# MouseGoggles_IRLED-1-5.net
KiCad netlist of a schematic drawn in EAGLE
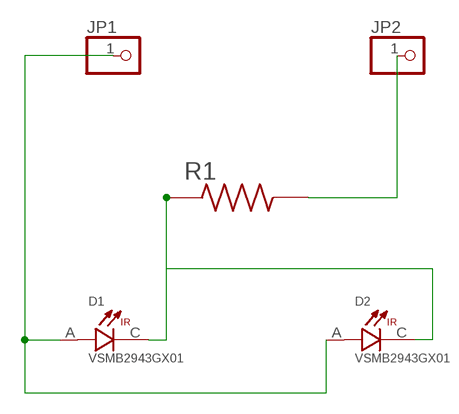
[diagram p0: schematic, sheet 1]

(export (version "E")
  (design (tool "Eeschema 10.0.6"))
  (components
    (comp (ref "D1")
      (value "VSMB2943GX01")
      (footprint "eagle-import:DIO_VSMB2943GX01")
      (fields (field (name "MANUFACTURER") "VISHAY"))
      (libsource (lib "eagle-import") (part "VSMB2943GX01"))
    )
    (comp (ref "D2")
      (value "VSMB2943GX01")
      (footprint "eagle-import:DIO_VSMB2943GX01")
      (fields (field (name "MANUFACTURER") "VISHAY"))
      (libsource (lib "eagle-import") (part "VSMB2943GX01"))
    )
    (comp (ref "JP1")
      (value "PINHD-1X1")
      (footprint "eagle-import:1X01")
      (libsource (lib "eagle-import") (part "PINHD-1X1"))
    )
    (comp (ref "JP2")
      (value "PINHD-1X1")
      (footprint "eagle-import:1X01")
      (libsource (lib "eagle-import") (part "PINHD-1X1"))
    )
    (comp (ref "R1")
      (value "RC0805FR-07100RL")
      (footprint "eagle-import:RESC2012X60N")
      (libsource (lib "eagle-import") (part "RC0805FR-07100RL"))
    )
  )
  (nets
    (net (code "1") (name "Net-(D1-PadA)") (class "Default")
      (node (ref "D1") (pin "A") (pinfunction "A_A") (pintype "passive"))
      (node (ref "D2") (pin "A") (pinfunction "A_A") (pintype "passive"))
      (node (ref "JP1") (pin "1") (pinfunction "1_1") (pintype "passive"))
    )
    (net (code "2") (name "Net-(D1-PadC)") (class "Default")
      (node (ref "D1") (pin "C") (pinfunction "C_C") (pintype "passive"))
      (node (ref "D2") (pin "C") (pinfunction "C_C") (pintype "passive"))
      (node (ref "R1") (pin "1") (pinfunction "1_1") (pintype "passive"))
    )
    (net (code "3") (name "Net-(JP2-Pad1)") (class "Default")
      (node (ref "JP2") (pin "1") (pinfunction "1_1") (pintype "passive"))
      (node (ref "R1") (pin "2") (pinfunction "2_2") (pintype "passive"))
    )
  )
)
